# 06_ETHERNET.net
KiCad netlist of a schematic drawn in Altium Designer
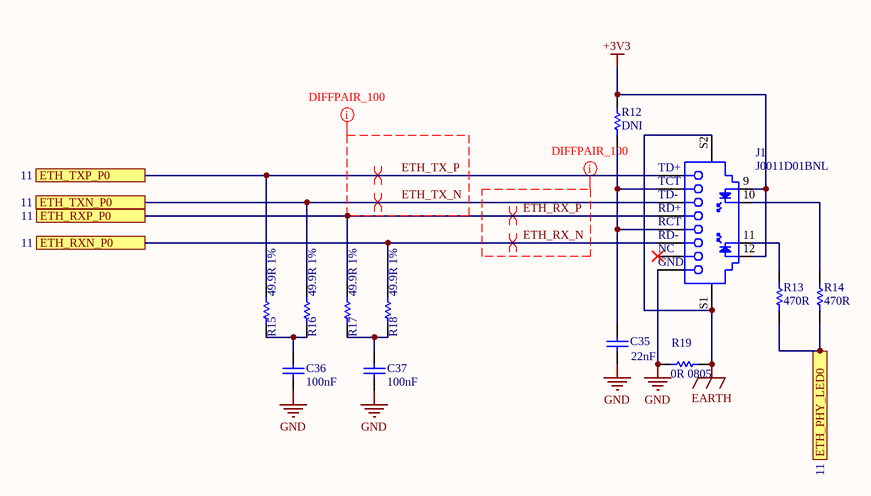
[diagram p0: 06. ETHERNET.SchDoc]

(export (version "E")
  (design (tool "Eeschema 10.0.6"))
  (components
    (comp (ref "C35")
      (value "22nF")
      (footprint "CAPC1005X60X30LL05T10")
      (fields (field (name "PART NUMBER") "GRM155R71H223KA12D") (field (name "MANUFACTURER") "Murata"))
      (libsource (lib "AM3358_DEV_BOARD") (part "CAP"))
    )
    (comp (ref "C36")
      (value "100nF")
      (footprint "CAPC1005X60X30LL05T10")
      (description "Chip Capacitor, 0.1 uF, +/- 10%, 16 V, -55 to 125 degC, 0402 (1005 Metric), RoHS, Tape and Reel")
      (fields (field (name "VOLTAGE") "16V") (field (name "TOLERANCE") "10%"))
      (libsource (lib "AM3358_DEV_BOARD") (part "CAP-NP-2"))
    )
    (comp (ref "C37")
      (value "100nF")
      (footprint "CAPC1005X60X30LL05T10")
      (description "Chip Capacitor, 0.1 uF, +/- 10%, 16 V, -55 to 125 degC, 0402 (1005 Metric), RoHS, Tape and Reel")
      (fields (field (name "VOLTAGE") "16V") (field (name "TOLERANCE") "10%"))
      (libsource (lib "AM3358_DEV_BOARD") (part "CAP-NP-2"))
    )
    (comp (ref "J1")
      (value "J0011D01BNL")
      (footprint "J0011D01BNL 1PORT 100 BASE-TX")
      (fields (field (name "MANUFACTURER") "Pulse Electronics"))
      (libsource (lib "AM3358_DEV_BOARD") (part "RJ45-12-2SHLD_F"))
    )
    (comp (ref "R12")
      (value "DNI")
      (footprint "RESC1005X40X25LL05T05")
      (fields (field (name "PART NUMBER") "CRCW040210R0FKEDHP") (field (name "MANUFACTURER") "Vishay Dale"))
      (libsource (lib "AM3358_DEV_BOARD") (part "RES"))
    )
    (comp (ref "R13")
      (value "470R")
      (footprint "RESC1005X40X25LL05T05")
      (fields (field (name "PART NUMBER") "CRCW0603470RFKEA") (field (name "MANUFACTURER") "Vishay Dale"))
      (libsource (lib "AM3358_DEV_BOARD") (part "RES"))
    )
    (comp (ref "R14")
      (value "470R")
      (footprint "RESC1005X40X25LL05T05")
      (fields (field (name "PART NUMBER") "CRCW0603470RFKEA") (field (name "MANUFACTURER") "Vishay Dale"))
      (libsource (lib "AM3358_DEV_BOARD") (part "RES"))
    )
    (comp (ref "R15")
      (value "49.9R 1%")
      (footprint "RESC1005X40X25LL05T05")
      (description "Precision Thick Film Chip Resistors")
      (fields (field (name "MANUFACTURER") "Panasonic") (field (name "PART NUMBER") "ERJ-2RKF49R9X"))
      (libsource (lib "AM3358_DEV_BOARD") (part "RES"))
    )
    (comp (ref "R16")
      (value "49.9R 1%")
      (footprint "RESC1005X40X25LL05T05")
      (description "Precision Thick Film Chip Resistors")
      (fields (field (name "MANUFACTURER") "Panasonic") (field (name "PART NUMBER") "ERJ-2RKF49R9X"))
      (libsource (lib "AM3358_DEV_BOARD") (part "RES"))
    )
    (comp (ref "R17")
      (value "49.9R 1%")
      (footprint "RESC1005X40X25LL05T05")
      (description "Precision Thick Film Chip Resistors")
      (fields (field (name "MANUFACTURER") "Panasonic") (field (name "PART NUMBER") "ERJ-2RKF49R9X"))
      (libsource (lib "AM3358_DEV_BOARD") (part "RES"))
    )
    (comp (ref "R18")
      (value "49.9R 1%")
      (footprint "RESC1005X40X25LL05T05")
      (description "Precision Thick Film Chip Resistors")
      (fields (field (name "MANUFACTURER") "Panasonic") (field (name "PART NUMBER") "ERJ-2RKF49R9X"))
      (libsource (lib "AM3358_DEV_BOARD") (part "RES"))
    )
    (comp (ref "R19")
      (value "0R 0805")
      (footprint "RESC2013X50X30LL20T20")
      (fields (field (name "MANUFACTURER") "Vishay Dale") (field (name "PART NUMBER") "CRCW08050000Z0EA"))
      (libsource (lib "Altium Content Vault") (part "RES"))
    )
  )
  (nets
    (net (code "1") (name "+3V3") (class "Default")
      (node (ref "J1") (pin "12") (pinfunction "12_12") (pintype "passive"))
      (node (ref "J1") (pin "9") (pinfunction "9_9") (pintype "passive"))
      (node (ref "R12") (pin "2") (pinfunction "2_2") (pintype "passive"))
    )
    (net (code "2") (name "/ETH_PHY_LED0") (class "Default")
      (node (ref "R13") (pin "1") (pinfunction "1_1") (pintype "passive"))
      (node (ref "R14") (pin "1") (pinfunction "1_1") (pintype "passive"))
    )
    (net (code "3") (name "/ETH_RX_N") (class "Default")
      (node (ref "J1") (pin "6") (pinfunction "RD-_6") (pintype "passive"))
      (node (ref "R18") (pin "2") (pinfunction "2_2") (pintype "passive"))
    )
    (net (code "4") (name "/ETH_RX_P") (class "Default")
      (node (ref "J1") (pin "4") (pinfunction "RD+_4") (pintype "passive"))
      (node (ref "R17") (pin "2") (pinfunction "2_2") (pintype "passive"))
    )
    (net (code "5") (name "/ETH_TX_N") (class "Default")
      (node (ref "J1") (pin "3") (pinfunction "TD-_3") (pintype "passive"))
      (node (ref "R16") (pin "2") (pinfunction "2_2") (pintype "passive"))
    )
    (net (code "6") (name "/ETH_TX_P") (class "Default")
      (node (ref "J1") (pin "1") (pinfunction "TD+_1") (pintype "passive"))
      (node (ref "R15") (pin "2") (pinfunction "2_2") (pintype "passive"))
    )
    (net (code "7") (name "EARTH") (class "Default")
      (node (ref "J1") (pin "S1") (pinfunction "S1_S1") (pintype "passive"))
      (node (ref "J1") (pin "S2") (pinfunction "S2_S2") (pintype "passive"))
      (node (ref "R19") (pin "2") (pinfunction "2_2") (pintype "passive"))
    )
    (net (code "8") (name "GND") (class "Default")
      (node (ref "C35") (pin "1") (pinfunction "1_1") (pintype "passive"))
      (node (ref "C36") (pin "1") (pinfunction "1_1") (pintype "passive"))
      (node (ref "C37") (pin "1") (pinfunction "1_1") (pintype "passive"))
      (node (ref "J1") (pin "8") (pinfunction "GND_8") (pintype "passive"))
      (node (ref "R19") (pin "1") (pinfunction "1_1") (pintype "passive"))
    )
    (net (code "9") (name "Net-(C36-Pad2)") (class "Default")
      (node (ref "C36") (pin "2") (pinfunction "2_2") (pintype "passive"))
      (node (ref "R15") (pin "1") (pinfunction "1_1") (pintype "passive"))
      (node (ref "R16") (pin "1") (pinfunction "1_1") (pintype "passive"))
    )
    (net (code "10") (name "Net-(C37-Pad2)") (class "Default")
      (node (ref "C37") (pin "2") (pinfunction "2_2") (pintype "passive"))
      (node (ref "R17") (pin "1") (pinfunction "1_1") (pintype "passive"))
      (node (ref "R18") (pin "1") (pinfunction "1_1") (pintype "passive"))
    )
    (net (code "11") (name "Net-(J1-Pad10)") (class "Default")
      (node (ref "J1") (pin "10") (pinfunction "10_10") (pintype "passive"))
      (node (ref "R14") (pin "2") (pinfunction "2_2") (pintype "passive"))
    )
    (net (code "12") (name "Net-(J1-Pad11)") (class "Default")
      (node (ref "J1") (pin "11") (pinfunction "11_11") (pintype "passive"))
      (node (ref "R13") (pin "2") (pinfunction "2_2") (pintype "passive"))
    )
    (net (code "13") (name "Net-(J1-RCT)") (class "Default")
      (node (ref "C35") (pin "2") (pinfunction "2_2") (pintype "passive"))
      (node (ref "J1") (pin "2") (pinfunction "TCT_2") (pintype "passive"))
      (node (ref "J1") (pin "5") (pinfunction "RCT_5") (pintype "passive"))
      (node (ref "R12") (pin "1") (pinfunction "1_1") (pintype "passive"))
    )
    (net (code "14") (name "unconnected-(J1-NC-Pad7)") (class "Default")
      (node (ref "J1") (pin "7") (pinfunction "NC_7") (pintype "passive+no_connect"))
    )
  )
)
